# nf10_addon.net
KiCad netlist of a schematic drawn in Altium Designer
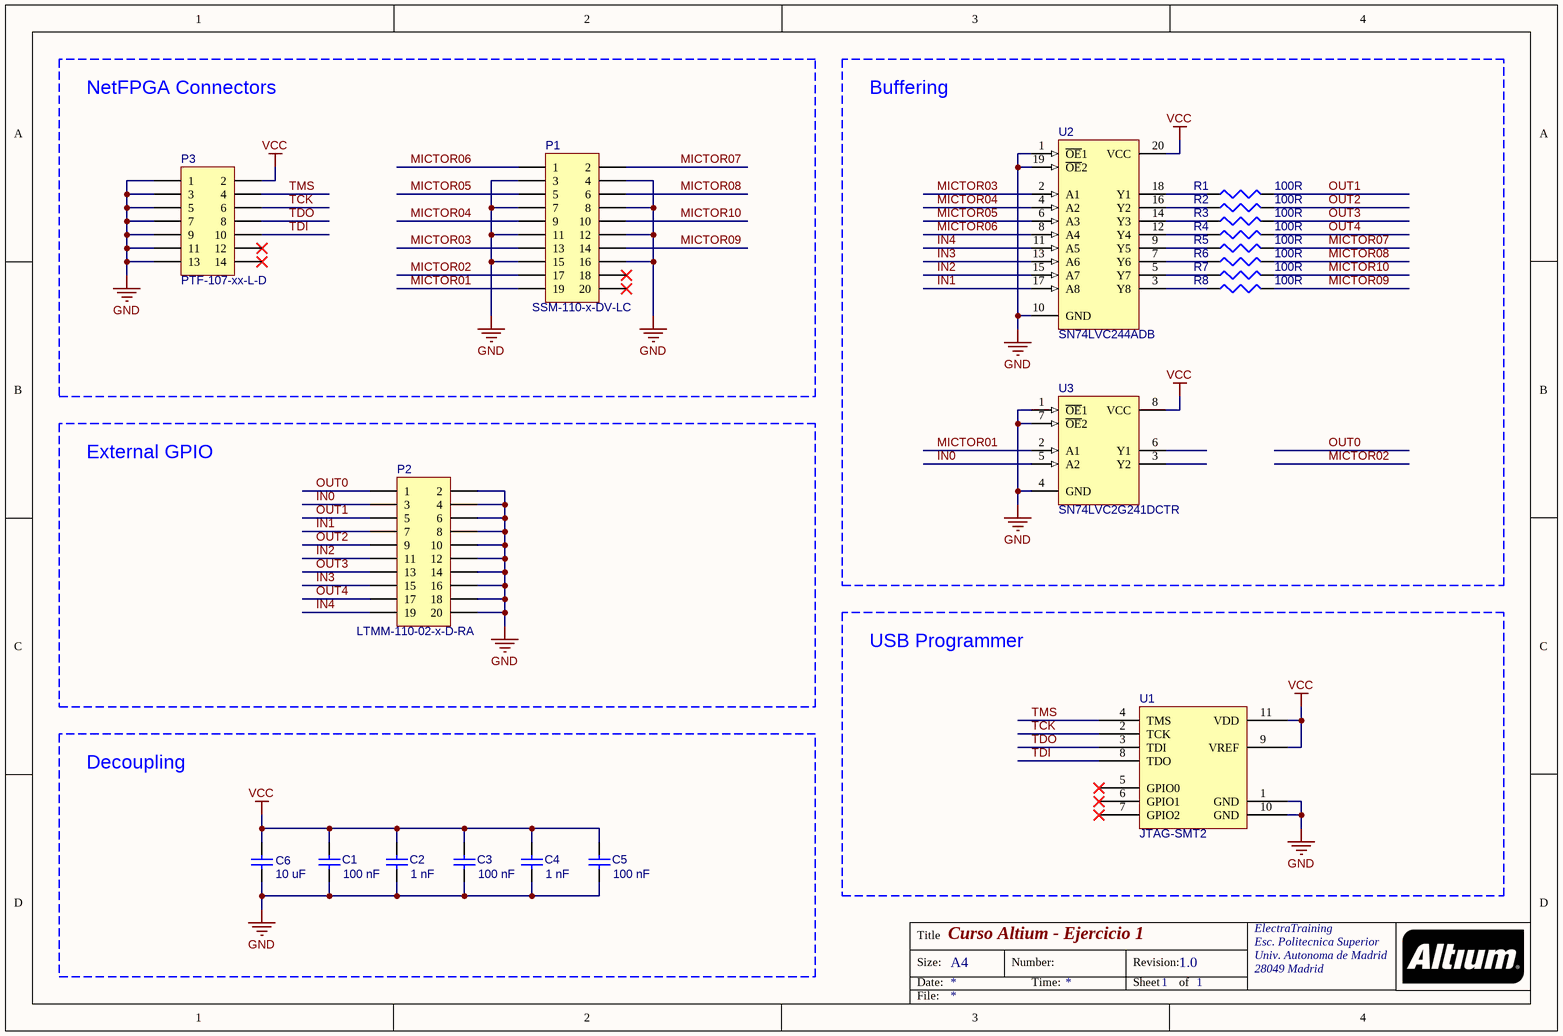
[diagram p0: nf10_addon.SchDoc]

(export (version "E")
  (design (tool "Eeschema 10.0.6"))
  (components
    (comp (ref "C1")
      (value "100 nF")
      (footprint "CAPC0603(1608)100_N")
      (description "Capacitor")
      (fields (field (name "Comment") "Cap") (field (name "PUBLISHER") "Altium Limited"))
      (libsource (lib "Miscellaneous Devices") (part "Cap"))
    )
    (comp (ref "C2")
      (value "1 nF")
      (footprint "CAPC0603(1608)100_N")
      (description "Capacitor")
      (fields (field (name "Comment") "Cap") (field (name "PUBLISHER") "Altium Limited"))
      (libsource (lib "Miscellaneous Devices") (part "Cap"))
    )
    (comp (ref "C3")
      (value "100 nF")
      (footprint "CAPC0603(1608)100_N")
      (description "Capacitor")
      (fields (field (name "Comment") "Cap") (field (name "PUBLISHER") "Altium Limited"))
      (libsource (lib "Miscellaneous Devices") (part "Cap"))
    )
    (comp (ref "C4")
      (value "1 nF")
      (footprint "CAPC0603(1608)100_N")
      (description "Capacitor")
      (fields (field (name "Comment") "Cap") (field (name "PUBLISHER") "Altium Limited"))
      (libsource (lib "Miscellaneous Devices") (part "Cap"))
    )
    (comp (ref "C5")
      (value "100 nF")
      (footprint "CAPC0603(1608)100_N")
      (description "Capacitor")
      (fields (field (name "Comment") "Cap") (field (name "PUBLISHER") "Altium Limited"))
      (libsource (lib "Miscellaneous Devices") (part "Cap"))
    )
    (comp (ref "C6")
      (value "10 uF")
      (footprint "CAPC1206(3216)100_N")
      (description "Capacitor")
      (fields (field (name "Comment") "Cap") (field (name "PUBLISHER") "Altium Limited"))
      (libsource (lib "Miscellaneous Devices") (part "Cap"))
    )
    (comp (ref "P1")
      (value "SSM-110-x-DV-LC")
      (footprint "SSM-110-X-DV-LC")
      (description "Samtec SSM-110-x-DV-LC")
      (fields (field (name "PUBLISHER") "Altium Limited"))
      (libsource (lib "nf10_addon") (part "SSM-110-x-DV-LC"))
    )
    (comp (ref "P2")
      (value "LTMM-110-02-x-D-RA")
      (footprint "LTMM-110-02-X-D-RA")
      (description "Samtec LTMM-110-02-x-D-RA")
      (fields (field (name "PUBLISHER") "Altium Limited"))
      (libsource (lib "nf10_addon") (part "LTMM-110-02-x-D-RA"))
    )
    (comp (ref "P3")
      (value "PTF-107-xx-L-D")
      (footprint "PTF-107-XX-L-D")
      (description "Samtec PTF-107-xx-L-D")
      (fields (field (name "PUBLISHER") "Altium Limited"))
      (libsource (lib "nf10_addon") (part "PTF-107-xx-L-D"))
    )
    (comp (ref "R1")
      (value "100R")
      (footprint "RESC0603(1608)_N")
      (description "Resistor")
      (fields (field (name "Comment") "Res3") (field (name "PUBLISHER") "Altium Limited"))
      (libsource (lib "Miscellaneous Devices") (part "Res3"))
    )
    (comp (ref "R2")
      (value "100R")
      (footprint "RESC0603(1608)_N")
      (description "Resistor")
      (fields (field (name "Comment") "Res3") (field (name "PUBLISHER") "Altium Limited"))
      (libsource (lib "Miscellaneous Devices") (part "Res3"))
    )
    (comp (ref "R3")
      (value "100R")
      (footprint "RESC0603(1608)_N")
      (description "Resistor")
      (fields (field (name "Comment") "Res3") (field (name "PUBLISHER") "Altium Limited"))
      (libsource (lib "Miscellaneous Devices") (part "Res3"))
    )
    (comp (ref "R4")
      (value "100R")
      (footprint "RESC0603(1608)_N")
      (description "Resistor")
      (fields (field (name "Comment") "Res3") (field (name "PUBLISHER") "Altium Limited"))
      (libsource (lib "Miscellaneous Devices") (part "Res3"))
    )
    (comp (ref "R5")
      (value "100R")
      (footprint "RESC0603(1608)_N")
      (description "Resistor")
      (fields (field (name "Comment") "Res3") (field (name "PUBLISHER") "Altium Limited"))
      (libsource (lib "Miscellaneous Devices") (part "Res3"))
    )
    (comp (ref "R6")
      (value "100R")
      (footprint "RESC0603(1608)_N")
      (description "Resistor")
      (fields (field (name "Comment") "Res3") (field (name "PUBLISHER") "Altium Limited"))
      (libsource (lib "Miscellaneous Devices") (part "Res3"))
    )
    (comp (ref "R7")
      (value "100R")
      (footprint "RESC0603(1608)_N")
      (description "Resistor")
      (fields (field (name "Comment") "Res3") (field (name "PUBLISHER") "Altium Limited"))
      (libsource (lib "Miscellaneous Devices") (part "Res3"))
    )
    (comp (ref "R8")
      (value "100R")
      (footprint "RESC0603(1608)_N")
      (description "Resistor")
      (fields (field (name "Comment") "Res3") (field (name "PUBLISHER") "Altium Limited"))
      (libsource (lib "Miscellaneous Devices") (part "Res3"))
    )
    (comp (ref "U1")
      (value "JTAG-SMT2")
      (footprint "JTAG-SMT2")
      (libsource (lib "NetFPGA10G_Addon") (part "JTAG_SMT2"))
    )
    (comp (ref "U2")
      (value "SN74LVC244ADB")
      (footprint "DB020_N")
      (description "Octal Buffer/Driver with 3-State Outputs")
      (fields (field (name "PUBLISHER") "Altium Limited"))
      (libsource (lib "TI Logic Buffer Line Driver") (part "SN74LVC244ADB"))
    )
    (comp (ref "U3")
      (value "SN74LVC2G241DCTR")
      (footprint "DCT08_N")
      (description "Quadruple Bus Buffer Gate with 3- State Outputs")
      (fields (field (name "PUBLISHER") "Altium Limited"))
      (libsource (lib "nf10_addon") (part "SN74LVC2G241DCTR"))
    )
  )
  (nets
    (net (code "1") (name "/IN0") (class "Default")
      (node (ref "P2") (pin "3") (pinfunction "3_3") (pintype "passive"))
      (node (ref "U3") (pin "5") (pinfunction "A2_5") (pintype "input"))
    )
    (net (code "2") (name "/IN1") (class "Default")
      (node (ref "P2") (pin "7") (pinfunction "7_7") (pintype "passive"))
      (node (ref "U2") (pin "17") (pinfunction "A8_17") (pintype "input"))
    )
    (net (code "3") (name "/IN2") (class "Default")
      (node (ref "P2") (pin "11") (pinfunction "11_11") (pintype "passive"))
      (node (ref "U2") (pin "15") (pinfunction "A7_15") (pintype "input"))
    )
    (net (code "4") (name "/IN3") (class "Default")
      (node (ref "P2") (pin "15") (pinfunction "15_15") (pintype "passive"))
      (node (ref "U2") (pin "13") (pinfunction "A6_13") (pintype "input"))
    )
    (net (code "5") (name "/IN4") (class "Default")
      (node (ref "P2") (pin "19") (pinfunction "19_19") (pintype "passive"))
      (node (ref "U2") (pin "11") (pinfunction "A5_11") (pintype "input"))
    )
    (net (code "6") (name "/MICTOR01") (class "Default")
      (node (ref "P1") (pin "19") (pinfunction "19_19") (pintype "passive"))
      (node (ref "U3") (pin "2") (pinfunction "A1_2") (pintype "input"))
    )
    (net (code "7") (name "/MICTOR02") (class "Default")
      (node (ref "P1") (pin "17") (pinfunction "17_17") (pintype "passive"))
    )
    (net (code "8") (name "/MICTOR03") (class "Default")
      (node (ref "P1") (pin "13") (pinfunction "13_13") (pintype "passive"))
      (node (ref "U2") (pin "2") (pinfunction "A1_2") (pintype "input"))
    )
    (net (code "9") (name "/MICTOR04") (class "Default")
      (node (ref "P1") (pin "9") (pinfunction "9_9") (pintype "passive"))
      (node (ref "U2") (pin "4") (pinfunction "A2_4") (pintype "input"))
    )
    (net (code "10") (name "/MICTOR05") (class "Default")
      (node (ref "P1") (pin "5") (pinfunction "5_5") (pintype "passive"))
      (node (ref "U2") (pin "6") (pinfunction "A3_6") (pintype "input"))
    )
    (net (code "11") (name "/MICTOR06") (class "Default")
      (node (ref "P1") (pin "1") (pinfunction "1_1") (pintype "passive"))
      (node (ref "U2") (pin "8") (pinfunction "A4_8") (pintype "input"))
    )
    (net (code "12") (name "/MICTOR07") (class "Default")
      (node (ref "P1") (pin "2") (pinfunction "2_2") (pintype "passive"))
      (node (ref "R5") (pin "2") (pinfunction "2_2") (pintype "passive"))
    )
    (net (code "13") (name "/MICTOR08") (class "Default")
      (node (ref "P1") (pin "6") (pinfunction "6_6") (pintype "passive"))
      (node (ref "R6") (pin "2") (pinfunction "2_2") (pintype "passive"))
    )
    (net (code "14") (name "/MICTOR09") (class "Default")
      (node (ref "P1") (pin "14") (pinfunction "14_14") (pintype "passive"))
      (node (ref "R8") (pin "2") (pinfunction "2_2") (pintype "passive"))
    )
    (net (code "15") (name "/MICTOR10") (class "Default")
      (node (ref "P1") (pin "10") (pinfunction "10_10") (pintype "passive"))
      (node (ref "R7") (pin "2") (pinfunction "2_2") (pintype "passive"))
    )
    (net (code "16") (name "/OUT0") (class "Default")
      (node (ref "P2") (pin "1") (pinfunction "1_1") (pintype "passive"))
    )
    (net (code "17") (name "/OUT1") (class "Default")
      (node (ref "P2") (pin "5") (pinfunction "5_5") (pintype "passive"))
      (node (ref "R1") (pin "2") (pinfunction "2_2") (pintype "passive"))
    )
    (net (code "18") (name "/OUT2") (class "Default")
      (node (ref "P2") (pin "9") (pinfunction "9_9") (pintype "passive"))
      (node (ref "R2") (pin "2") (pinfunction "2_2") (pintype "passive"))
    )
    (net (code "19") (name "/OUT3") (class "Default")
      (node (ref "P2") (pin "13") (pinfunction "13_13") (pintype "passive"))
      (node (ref "R3") (pin "2") (pinfunction "2_2") (pintype "passive"))
    )
    (net (code "20") (name "/OUT4") (class "Default")
      (node (ref "P2") (pin "17") (pinfunction "17_17") (pintype "passive"))
      (node (ref "R4") (pin "2") (pinfunction "2_2") (pintype "passive"))
    )
    (net (code "21") (name "/TCK") (class "Default")
      (node (ref "P3") (pin "6") (pinfunction "6_6") (pintype "passive"))
      (node (ref "U1") (pin "2") (pinfunction "TCK_2") (pintype "passive"))
    )
    (net (code "22") (name "/TDI") (class "Default")
      (node (ref "P3") (pin "10") (pinfunction "10_10") (pintype "passive"))
      (node (ref "U1") (pin "8") (pinfunction "TDO_8") (pintype "passive"))
    )
    (net (code "23") (name "/TDO") (class "Default")
      (node (ref "P3") (pin "8") (pinfunction "8_8") (pintype "passive"))
      (node (ref "U1") (pin "3") (pinfunction "TDI_3") (pintype "passive"))
    )
    (net (code "24") (name "/TMS") (class "Default")
      (node (ref "P3") (pin "4") (pinfunction "4_4") (pintype "passive"))
      (node (ref "U1") (pin "4") (pinfunction "TMS_4") (pintype "passive"))
    )
    (net (code "25") (name "GND") (class "Default")
      (node (ref "C1") (pin "1") (pinfunction "1_1") (pintype "passive"))
      (node (ref "C2") (pin "1") (pinfunction "1_1") (pintype "passive"))
      (node (ref "C3") (pin "1") (pinfunction "1_1") (pintype "passive"))
      (node (ref "C4") (pin "1") (pinfunction "1_1") (pintype "passive"))
      (node (ref "C5") (pin "1") (pinfunction "1_1") (pintype "passive"))
      (node (ref "C6") (pin "1") (pinfunction "1_1") (pintype "passive"))
      (node (ref "P1") (pin "11") (pinfunction "11_11") (pintype "passive"))
      (node (ref "P1") (pin "12") (pinfunction "12_12") (pintype "passive"))
      (node (ref "P1") (pin "15") (pinfunction "15_15") (pintype "passive"))
      (node (ref "P1") (pin "16") (pinfunction "16_16") (pintype "passive"))
      (node (ref "P1") (pin "3") (pinfunction "3_3") (pintype "passive"))
      (node (ref "P1") (pin "4") (pinfunction "4_4") (pintype "passive"))
      (node (ref "P1") (pin "7") (pinfunction "7_7") (pintype "passive"))
      (node (ref "P1") (pin "8") (pinfunction "8_8") (pintype "passive"))
      (node (ref "P2") (pin "10") (pinfunction "10_10") (pintype "passive"))
      (node (ref "P2") (pin "12") (pinfunction "12_12") (pintype "passive"))
      (node (ref "P2") (pin "14") (pinfunction "14_14") (pintype "passive"))
      (node (ref "P2") (pin "16") (pinfunction "16_16") (pintype "passive"))
      (node (ref "P2") (pin "18") (pinfunction "18_18") (pintype "passive"))
      (node (ref "P2") (pin "2") (pinfunction "2_2") (pintype "passive"))
      (node (ref "P2") (pin "20") (pinfunction "20_20") (pintype "passive"))
      (node (ref "P2") (pin "4") (pinfunction "4_4") (pintype "passive"))
      (node (ref "P2") (pin "6") (pinfunction "6_6") (pintype "passive"))
      (node (ref "P2") (pin "8") (pinfunction "8_8") (pintype "passive"))
      (node (ref "P3") (pin "1") (pinfunction "1_1") (pintype "passive"))
      (node (ref "P3") (pin "11") (pinfunction "11_11") (pintype "passive"))
      (node (ref "P3") (pin "13") (pinfunction "13_13") (pintype "passive"))
      (node (ref "P3") (pin "3") (pinfunction "3_3") (pintype "passive"))
      (node (ref "P3") (pin "5") (pinfunction "5_5") (pintype "passive"))
      (node (ref "P3") (pin "7") (pinfunction "7_7") (pintype "passive"))
      (node (ref "P3") (pin "9") (pinfunction "9_9") (pintype "passive"))
      (node (ref "U1") (pin "1") (pinfunction "GND_1") (pintype "passive"))
      (node (ref "U1") (pin "10") (pinfunction "GND_10") (pintype "passive"))
      (node (ref "U2") (pin "1") (pinfunction "~{OE}1_1") (pintype "input"))
      (node (ref "U2") (pin "10") (pinfunction "GND_10") (pintype "power_in"))
      (node (ref "U2") (pin "19") (pinfunction "~{OE}2_19") (pintype "input"))
      (node (ref "U3") (pin "1") (pinfunction "~{OE}1_1") (pintype "input"))
      (node (ref "U3") (pin "4") (pinfunction "GND_4") (pintype "power_in"))
      (node (ref "U3") (pin "7") (pinfunction "~{OE}2_7") (pintype "input"))
    )
    (net (code "26") (name "Net-(U2-Y1)") (class "Default")
      (node (ref "R1") (pin "1") (pinfunction "1_1") (pintype "passive"))
      (node (ref "U2") (pin "18") (pinfunction "Y1_18") (pintype "tri_state"))
    )
    (net (code "27") (name "Net-(U2-Y2)") (class "Default")
      (node (ref "R2") (pin "1") (pinfunction "1_1") (pintype "passive"))
      (node (ref "U2") (pin "16") (pinfunction "Y2_16") (pintype "tri_state"))
    )
    (net (code "28") (name "Net-(U2-Y3)") (class "Default")
      (node (ref "R3") (pin "1") (pinfunction "1_1") (pintype "passive"))
      (node (ref "U2") (pin "14") (pinfunction "Y3_14") (pintype "tri_state"))
    )
    (net (code "29") (name "Net-(U2-Y4)") (class "Default")
      (node (ref "R4") (pin "1") (pinfunction "1_1") (pintype "passive"))
      (node (ref "U2") (pin "12") (pinfunction "Y4_12") (pintype "tri_state"))
    )
    (net (code "30") (name "Net-(U2-Y5)") (class "Default")
      (node (ref "R5") (pin "1") (pinfunction "1_1") (pintype "passive"))
      (node (ref "U2") (pin "9") (pinfunction "Y5_9") (pintype "tri_state"))
    )
    (net (code "31") (name "Net-(U2-Y6)") (class "Default")
      (node (ref "R6") (pin "1") (pinfunction "1_1") (pintype "passive"))
      (node (ref "U2") (pin "7") (pinfunction "Y6_7") (pintype "tri_state"))
    )
    (net (code "32") (name "Net-(U2-Y7)") (class "Default")
      (node (ref "R7") (pin "1") (pinfunction "1_1") (pintype "passive"))
      (node (ref "U2") (pin "5") (pinfunction "Y7_5") (pintype "tri_state"))
    )
    (net (code "33") (name "Net-(U2-Y8)") (class "Default")
      (node (ref "R8") (pin "1") (pinfunction "1_1") (pintype "passive"))
      (node (ref "U2") (pin "3") (pinfunction "Y8_3") (pintype "tri_state"))
    )
    (net (code "34") (name "VCC") (class "Default")
      (node (ref "C1") (pin "2") (pinfunction "2_2") (pintype "passive"))
      (node (ref "C2") (pin "2") (pinfunction "2_2") (pintype "passive"))
      (node (ref "C3") (pin "2") (pinfunction "2_2") (pintype "passive"))
      (node (ref "C4") (pin "2") (pinfunction "2_2") (pintype "passive"))
      (node (ref "C5") (pin "2") (pinfunction "2_2") (pintype "passive"))
      (node (ref "C6") (pin "2") (pinfunction "2_2") (pintype "passive"))
      (node (ref "P3") (pin "2") (pinfunction "2_2") (pintype "passive"))
      (node (ref "U1") (pin "11") (pinfunction "VDD_11") (pintype "passive"))
      (node (ref "U1") (pin "9") (pinfunction "VREF_9") (pintype "passive"))
      (node (ref "U2") (pin "20") (pinfunction "VCC_20") (pintype "power_in"))
      (node (ref "U3") (pin "8") (pinfunction "VCC_8") (pintype "power_in"))
    )
    (net (code "35") (name "unconnected-(P1-Pad18)") (class "Default")
      (node (ref "P1") (pin "18") (pinfunction "18_18") (pintype "passive+no_connect"))
    )
    (net (code "36") (name "unconnected-(P1-Pad20)") (class "Default")
      (node (ref "P1") (pin "20") (pinfunction "20_20") (pintype "passive+no_connect"))
    )
    (net (code "37") (name "unconnected-(P3-Pad12)") (class "Default")
      (node (ref "P3") (pin "12") (pinfunction "12_12") (pintype "passive+no_connect"))
    )
    (net (code "38") (name "unconnected-(P3-Pad14)") (class "Default")
      (node (ref "P3") (pin "14") (pinfunction "14_14") (pintype "passive+no_connect"))
    )
    (net (code "39") (name "unconnected-(U1-GPIO0-Pad5)") (class "Default")
      (node (ref "U1") (pin "5") (pinfunction "GPIO0_5") (pintype "passive+no_connect"))
    )
    (net (code "40") (name "unconnected-(U1-GPIO1-Pad6)") (class "Default")
      (node (ref "U1") (pin "6") (pinfunction "GPIO1_6") (pintype "passive+no_connect"))
    )
    (net (code "41") (name "unconnected-(U1-GPIO2-Pad7)") (class "Default")
      (node (ref "U1") (pin "7") (pinfunction "GPIO2_7") (pintype "passive+no_connect"))
    )
    (net (code "42") (name "unconnected-(U3-Y1-Pad6)") (class "Default")
      (node (ref "U3") (pin "6") (pinfunction "Y1_6") (pintype "tri_state"))
    )
    (net (code "43") (name "unconnected-(U3-Y2-Pad3)") (class "Default")
      (node (ref "U3") (pin "3") (pinfunction "Y2_3") (pintype "tri_state"))
    )
  )
)
